# Raspberry.net
KiCad netlist of a schematic drawn in Altium Designer
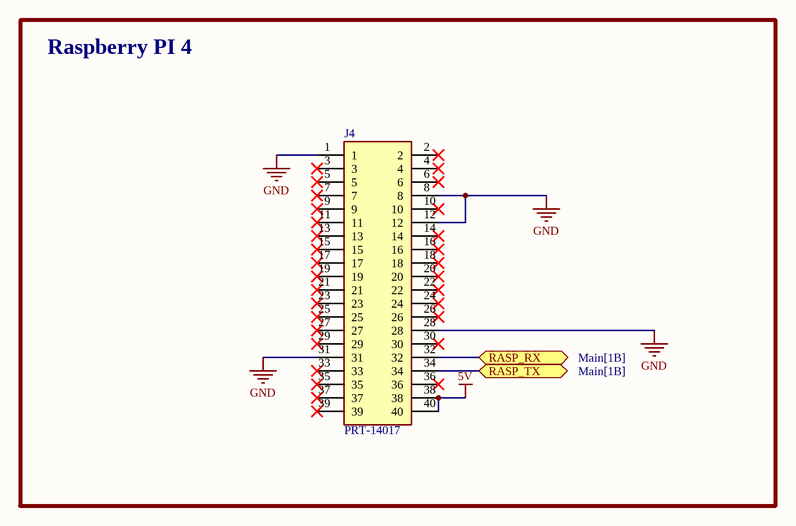
[diagram p0: Raspberry.SchDoc]

(export (version "E")
  (design (tool "Eeschema 10.0.6"))
  (components
    (comp (ref "J4")
      (value "PRT-14017")
      (footprint "roboime:RHDR40W64P254_2X20_5130X500X1375P")
      (description "Connector")
      (fields (field (name "MOUSER PART NUMBER") "474-PRT-14017"))
      (libsource (lib "roboime") (part "PRT-14017"))
    )
  )
  (nets
    (net (code "1") (name "/RASP_RX") (class "Default")
      (node (ref "J4") (pin "32") (pinfunction "32_32") (pintype "passive"))
    )
    (net (code "2") (name "/RASP_TX") (class "Default")
      (node (ref "J4") (pin "34") (pinfunction "34_34") (pintype "passive"))
    )
    (net (code "3") (name "5V") (class "Default")
      (node (ref "J4") (pin "38") (pinfunction "38_38") (pintype "passive"))
      (node (ref "J4") (pin "40") (pinfunction "40_40") (pintype "passive"))
    )
    (net (code "4") (name "GND") (class "Default")
      (node (ref "J4") (pin "1") (pinfunction "1_1") (pintype "passive"))
      (node (ref "J4") (pin "12") (pinfunction "12_12") (pintype "passive"))
      (node (ref "J4") (pin "28") (pinfunction "28_28") (pintype "passive"))
      (node (ref "J4") (pin "31") (pinfunction "31_31") (pintype "passive"))
      (node (ref "J4") (pin "8") (pinfunction "8_8") (pintype "passive"))
    )
    (net (code "5") (name "unconnected-(J4-Pad2)") (class "Default")
      (node (ref "J4") (pin "2") (pinfunction "2_2") (pintype "passive+no_connect"))
    )
    (net (code "6") (name "unconnected-(J4-Pad3)") (class "Default")
      (node (ref "J4") (pin "3") (pinfunction "3_3") (pintype "passive+no_connect"))
    )
    (net (code "7") (name "unconnected-(J4-Pad4)") (class "Default")
      (node (ref "J4") (pin "4") (pinfunction "4_4") (pintype "passive+no_connect"))
    )
    (net (code "8") (name "unconnected-(J4-Pad5)") (class "Default")
      (node (ref "J4") (pin "5") (pinfunction "5_5") (pintype "passive+no_connect"))
    )
    (net (code "9") (name "unconnected-(J4-Pad6)") (class "Default")
      (node (ref "J4") (pin "6") (pinfunction "6_6") (pintype "passive+no_connect"))
    )
    (net (code "10") (name "unconnected-(J4-Pad7)") (class "Default")
      (node (ref "J4") (pin "7") (pinfunction "7_7") (pintype "passive+no_connect"))
    )
    (net (code "11") (name "unconnected-(J4-Pad9)") (class "Default")
      (node (ref "J4") (pin "9") (pinfunction "9_9") (pintype "passive+no_connect"))
    )
    (net (code "12") (name "unconnected-(J4-Pad10)") (class "Default")
      (node (ref "J4") (pin "10") (pinfunction "10_10") (pintype "passive+no_connect"))
    )
    (net (code "13") (name "unconnected-(J4-Pad11)") (class "Default")
      (node (ref "J4") (pin "11") (pinfunction "11_11") (pintype "passive+no_connect"))
    )
    (net (code "14") (name "unconnected-(J4-Pad13)") (class "Default")
      (node (ref "J4") (pin "13") (pinfunction "13_13") (pintype "passive+no_connect"))
    )
    (net (code "15") (name "unconnected-(J4-Pad14)") (class "Default")
      (node (ref "J4") (pin "14") (pinfunction "14_14") (pintype "passive+no_connect"))
    )
    (net (code "16") (name "unconnected-(J4-Pad15)") (class "Default")
      (node (ref "J4") (pin "15") (pinfunction "15_15") (pintype "passive+no_connect"))
    )
    (net (code "17") (name "unconnected-(J4-Pad16)") (class "Default")
      (node (ref "J4") (pin "16") (pinfunction "16_16") (pintype "passive+no_connect"))
    )
    (net (code "18") (name "unconnected-(J4-Pad17)") (class "Default")
      (node (ref "J4") (pin "17") (pinfunction "17_17") (pintype "passive+no_connect"))
    )
    (net (code "19") (name "unconnected-(J4-Pad18)") (class "Default")
      (node (ref "J4") (pin "18") (pinfunction "18_18") (pintype "passive+no_connect"))
    )
    (net (code "20") (name "unconnected-(J4-Pad19)") (class "Default")
      (node (ref "J4") (pin "19") (pinfunction "19_19") (pintype "passive+no_connect"))
    )
    (net (code "21") (name "unconnected-(J4-Pad20)") (class "Default")
      (node (ref "J4") (pin "20") (pinfunction "20_20") (pintype "passive+no_connect"))
    )
    (net (code "22") (name "unconnected-(J4-Pad21)") (class "Default")
      (node (ref "J4") (pin "21") (pinfunction "21_21") (pintype "passive+no_connect"))
    )
    (net (code "23") (name "unconnected-(J4-Pad22)") (class "Default")
      (node (ref "J4") (pin "22") (pinfunction "22_22") (pintype "passive+no_connect"))
    )
    (net (code "24") (name "unconnected-(J4-Pad23)") (class "Default")
      (node (ref "J4") (pin "23") (pinfunction "23_23") (pintype "passive+no_connect"))
    )
    (net (code "25") (name "unconnected-(J4-Pad24)") (class "Default")
      (node (ref "J4") (pin "24") (pinfunction "24_24") (pintype "passive+no_connect"))
    )
    (net (code "26") (name "unconnected-(J4-Pad25)") (class "Default")
      (node (ref "J4") (pin "25") (pinfunction "25_25") (pintype "passive+no_connect"))
    )
    (net (code "27") (name "unconnected-(J4-Pad26)") (class "Default")
      (node (ref "J4") (pin "26") (pinfunction "26_26") (pintype "passive+no_connect"))
    )
    (net (code "28") (name "unconnected-(J4-Pad27)") (class "Default")
      (node (ref "J4") (pin "27") (pinfunction "27_27") (pintype "passive+no_connect"))
    )
    (net (code "29") (name "unconnected-(J4-Pad29)") (class "Default")
      (node (ref "J4") (pin "29") (pinfunction "29_29") (pintype "passive+no_connect"))
    )
    (net (code "30") (name "unconnected-(J4-Pad30)") (class "Default")
      (node (ref "J4") (pin "30") (pinfunction "30_30") (pintype "passive+no_connect"))
    )
    (net (code "31") (name "unconnected-(J4-Pad33)") (class "Default")
      (node (ref "J4") (pin "33") (pinfunction "33_33") (pintype "passive+no_connect"))
    )
    (net (code "32") (name "unconnected-(J4-Pad35)") (class "Default")
      (node (ref "J4") (pin "35") (pinfunction "35_35") (pintype "passive+no_connect"))
    )
    (net (code "33") (name "unconnected-(J4-Pad36)") (class "Default")
      (node (ref "J4") (pin "36") (pinfunction "36_36") (pintype "passive+no_connect"))
    )
    (net (code "34") (name "unconnected-(J4-Pad37)") (class "Default")
      (node (ref "J4") (pin "37") (pinfunction "37_37") (pintype "passive+no_connect"))
    )
    (net (code "35") (name "unconnected-(J4-Pad39)") (class "Default")
      (node (ref "J4") (pin "39") (pinfunction "39_39") (pintype "passive+no_connect"))
    )
  )
)
